# control_board-hall_test.net
KiCad netlist of a schematic drawn in EAGLE
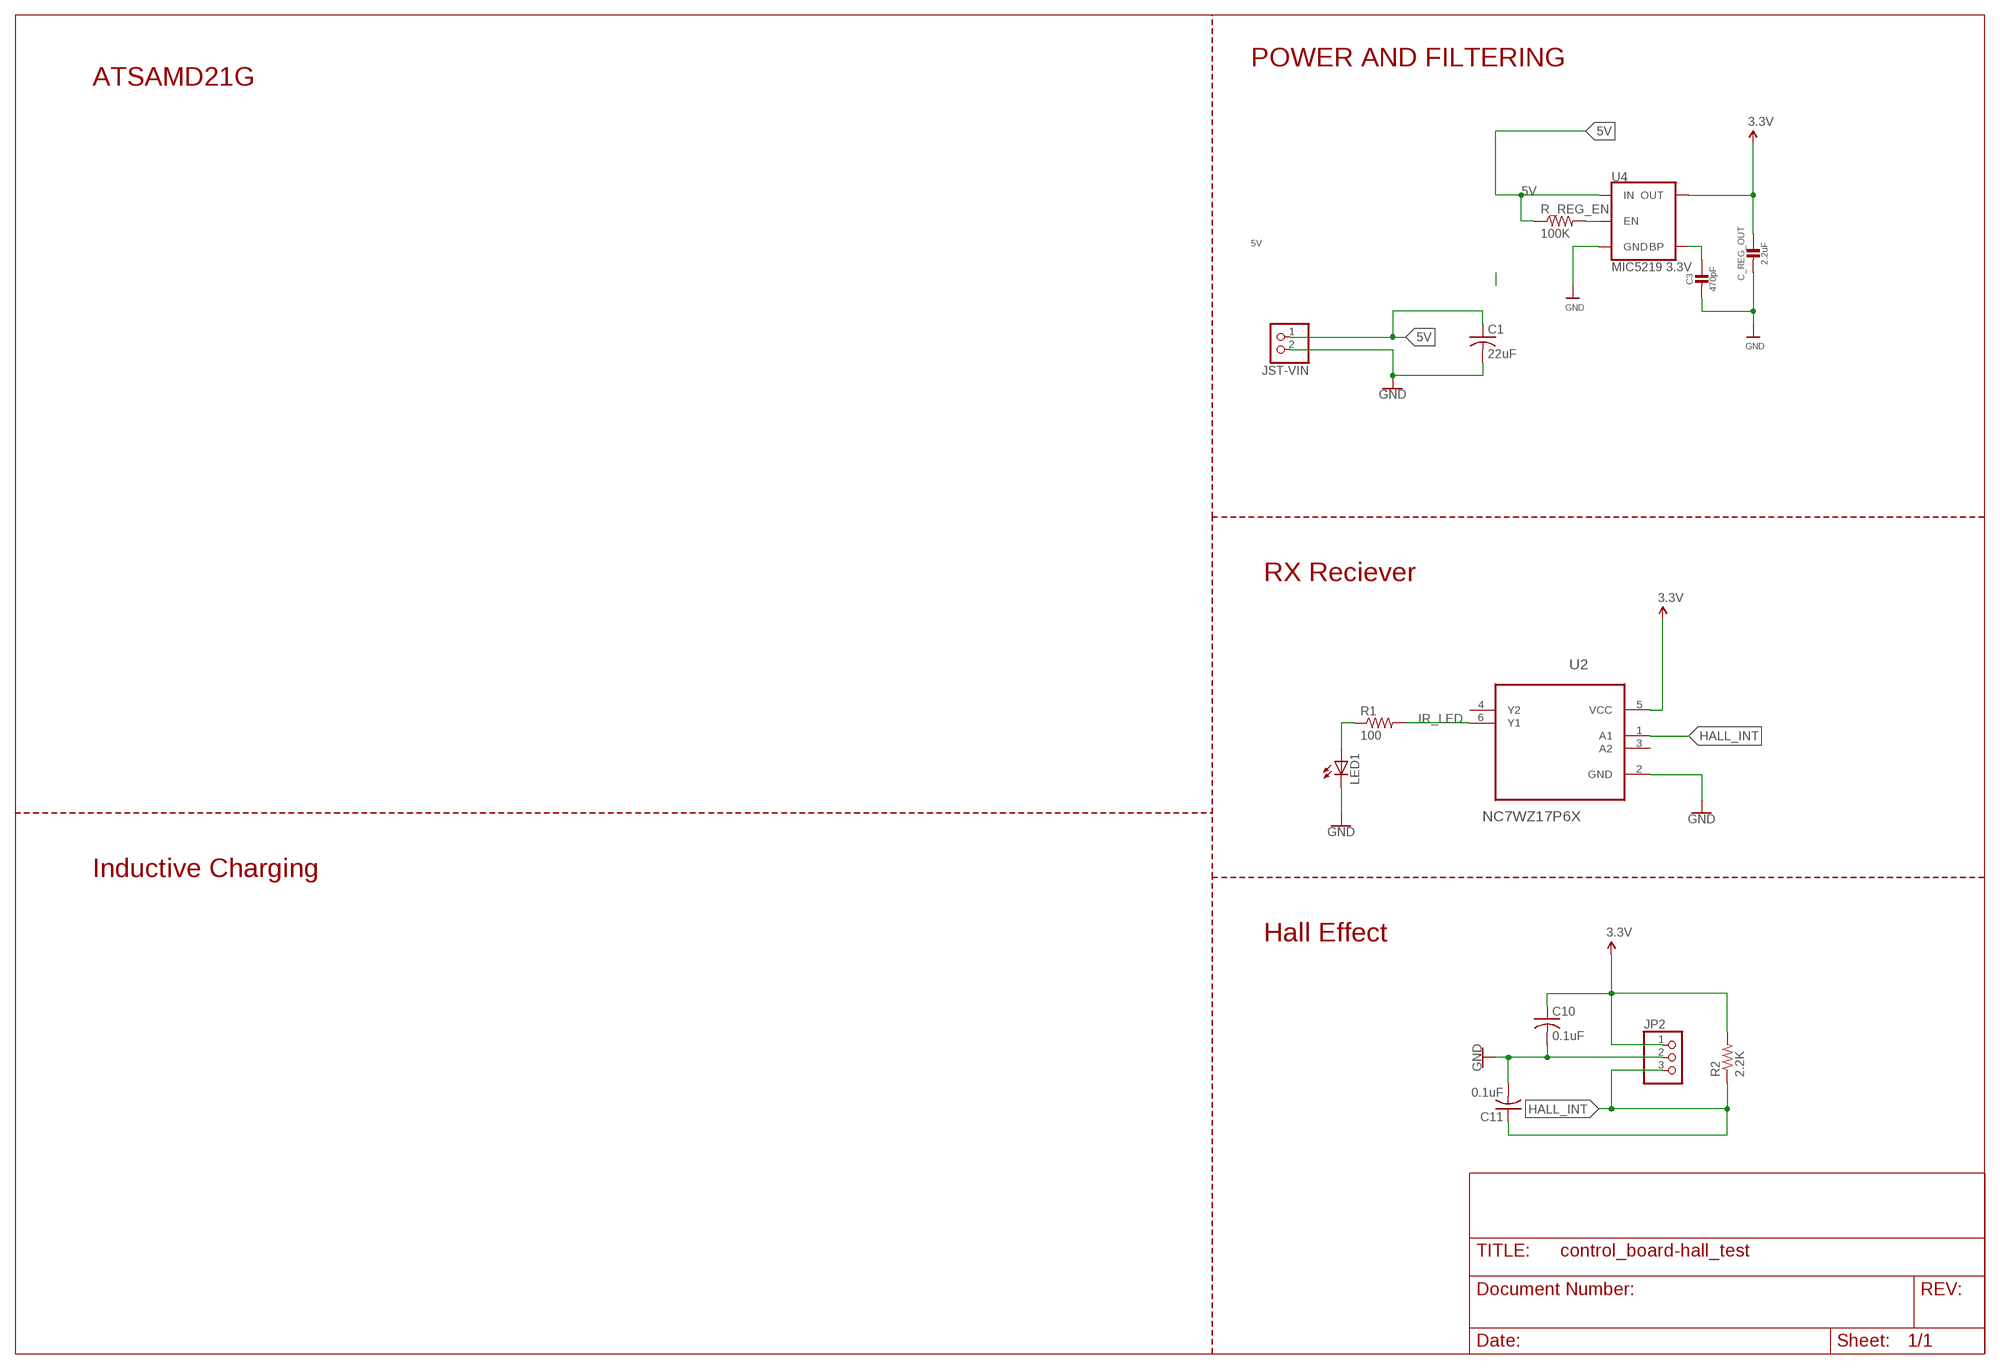
[diagram p0: schematic, sheet 1]

(export (version "E")
  (design (tool "Eeschema 10.0.6"))
  (components
    (comp (ref "C1")
      (value "22uF")
      (footprint "eagle-import:C1206")
      (libsource (lib "eagle-import") (part "C-USC1206"))
    )
    (comp (ref "C3")
      (value "470pF")
      (footprint "eagle-import:0603-NO")
      (libsource (lib "eagle-import") (part "CAP_CERAMIC0603_NO"))
    )
    (comp (ref "C10")
      (value "0.1uF")
      (footprint "eagle-import:C0603")
      (libsource (lib "eagle-import") (part "C-USC0603"))
    )
    (comp (ref "C11")
      (value "0.1uF")
      (footprint "eagle-import:C0603")
      (libsource (lib "eagle-import") (part "C-USC0603"))
    )
    (comp (ref "C_REG_OUT")
      (value "2.2uF")
      (footprint "eagle-import:0805-NO")
      (libsource (lib "eagle-import") (part "CAP_CERAMIC0805-NOOUTLINE"))
    )
    (comp (ref "JP2")
      (value "PINHD-1X3")
      (footprint "eagle-import:1X03")
      (libsource (lib "eagle-import") (part "PINHD-1X3"))
    )
    (comp (ref "JST-VIN")
      (value "JST_2PIN-THM-RA")
      (footprint "eagle-import:JST-PH-2-THM-RA")
      (libsource (lib "eagle-import") (part "JST_2PIN-THM-RA"))
    )
    (comp (ref "LED1")
      (value "LED3MM")
      (footprint "eagle-import:LED3MM")
      (libsource (lib "eagle-import") (part "LED3MM"))
    )
    (comp (ref "R1")
      (value "100")
      (footprint "eagle-import:0207_9")
      (libsource (lib "eagle-import") (part "R-US_0207/9"))
    )
    (comp (ref "R2")
      (value "2.2K")
      (footprint "eagle-import:0207_9")
      (libsource (lib "eagle-import") (part "R-US_0207/9"))
    )
    (comp (ref "R_REG_EN")
      (value "100K")
      (footprint "eagle-import:R0603")
      (libsource (lib "eagle-import") (part "R-US_R0603"))
    )
    (comp (ref "U2")
      (value "NC7WZ17P6X")
      (footprint "eagle-import:SOT65P210X110-6N")
      (fields (field (name "MF") "Fairchild Semiconductor"))
      (libsource (lib "eagle-import") (part "NC7WZ17P6X"))
    )
    (comp (ref "U4")
      (value "MIC5219 3.3V")
      (footprint "eagle-import:SOT23-5")
      (libsource (lib "eagle-import") (part "V_REG_MIC52193.3V"))
    )
  )
  (nets
    (net (code "1") (name "/IR_LED") (class "Default")
      (node (ref "R1") (pin "2") (pinfunction "2_2") (pintype "passive"))
      (node (ref "U2") (pin "6") (pinfunction "Y1_6") (pintype "output"))
    )
    (net (code "2") (name "3.3V") (class "Default")
      (node (ref "C10") (pin "1") (pinfunction "1_1") (pintype "passive"))
      (node (ref "C_REG_OUT") (pin "1") (pinfunction "1_1") (pintype "passive"))
      (node (ref "JP2") (pin "1") (pinfunction "1_1") (pintype "passive"))
      (node (ref "R2") (pin "2") (pinfunction "2_2") (pintype "passive"))
      (node (ref "U2") (pin "5") (pinfunction "VCC_5") (pintype "power_in"))
      (node (ref "U4") (pin "5") (pinfunction "OUT_5") (pintype "passive"))
    )
    (net (code "3") (name "5V") (class "Default")
      (node (ref "C1") (pin "1") (pinfunction "1_1") (pintype "passive"))
      (node (ref "JST-VIN") (pin "1") (pinfunction "2_1") (pintype "passive"))
      (node (ref "R_REG_EN") (pin "1") (pinfunction "1_1") (pintype "passive"))
      (node (ref "U4") (pin "1") (pinfunction "IN_1") (pintype "input"))
    )
    (net (code "4") (name "GND") (class "Default")
      (node (ref "C1") (pin "2") (pinfunction "2_2") (pintype "passive"))
      (node (ref "C10") (pin "2") (pinfunction "2_2") (pintype "passive"))
      (node (ref "C11") (pin "2") (pinfunction "2_2") (pintype "passive"))
      (node (ref "C3") (pin "2") (pinfunction "2_2") (pintype "passive"))
      (node (ref "C_REG_OUT") (pin "2") (pinfunction "2_2") (pintype "passive"))
      (node (ref "JP2") (pin "2") (pinfunction "2_2") (pintype "passive"))
      (node (ref "JST-VIN") (pin "2") (pinfunction "1_2") (pintype "passive"))
      (node (ref "LED1") (pin "K") (pinfunction "C_K") (pintype "passive"))
      (node (ref "U2") (pin "2") (pinfunction "GND_2") (pintype "passive"))
      (node (ref "U4") (pin "2") (pinfunction "GND_2") (pintype "input"))
    )
    (net (code "5") (name "HALL_INT") (class "Default")
      (node (ref "C11") (pin "1") (pinfunction "1_1") (pintype "passive"))
      (node (ref "JP2") (pin "3") (pinfunction "3_3") (pintype "passive"))
      (node (ref "R2") (pin "1") (pinfunction "1_1") (pintype "passive"))
      (node (ref "U2") (pin "1") (pinfunction "A1_1") (pintype "input"))
    )
    (net (code "6") (name "Net-(LED1-PadA)") (class "Default")
      (node (ref "LED1") (pin "A") (pinfunction "A_A") (pintype "passive"))
      (node (ref "R1") (pin "1") (pinfunction "1_1") (pintype "passive"))
    )
    (net (code "7") (name "Net-(U4-BP)") (class "Default")
      (node (ref "C3") (pin "1") (pinfunction "1_1") (pintype "passive"))
      (node (ref "U4") (pin "4") (pinfunction "BP_4") (pintype "input"))
    )
    (net (code "8") (name "Net-(U4-EN)") (class "Default")
      (node (ref "R_REG_EN") (pin "2") (pinfunction "2_2") (pintype "passive"))
      (node (ref "U4") (pin "3") (pinfunction "EN_3") (pintype "input"))
    )
    (net (code "9") (name "unconnected-(U2-A2-Pad3)") (class "Default")
      (node (ref "U2") (pin "3") (pinfunction "A2_3") (pintype "input"))
    )
    (net (code "10") (name "unconnected-(U2-Y2-Pad4)") (class "Default")
      (node (ref "U2") (pin "4") (pinfunction "Y2_4") (pintype "output"))
    )
  )
)
